# SCH_keyboard_2024-02-28.net
KiCad netlist of a schematic drawn in EasyEDA
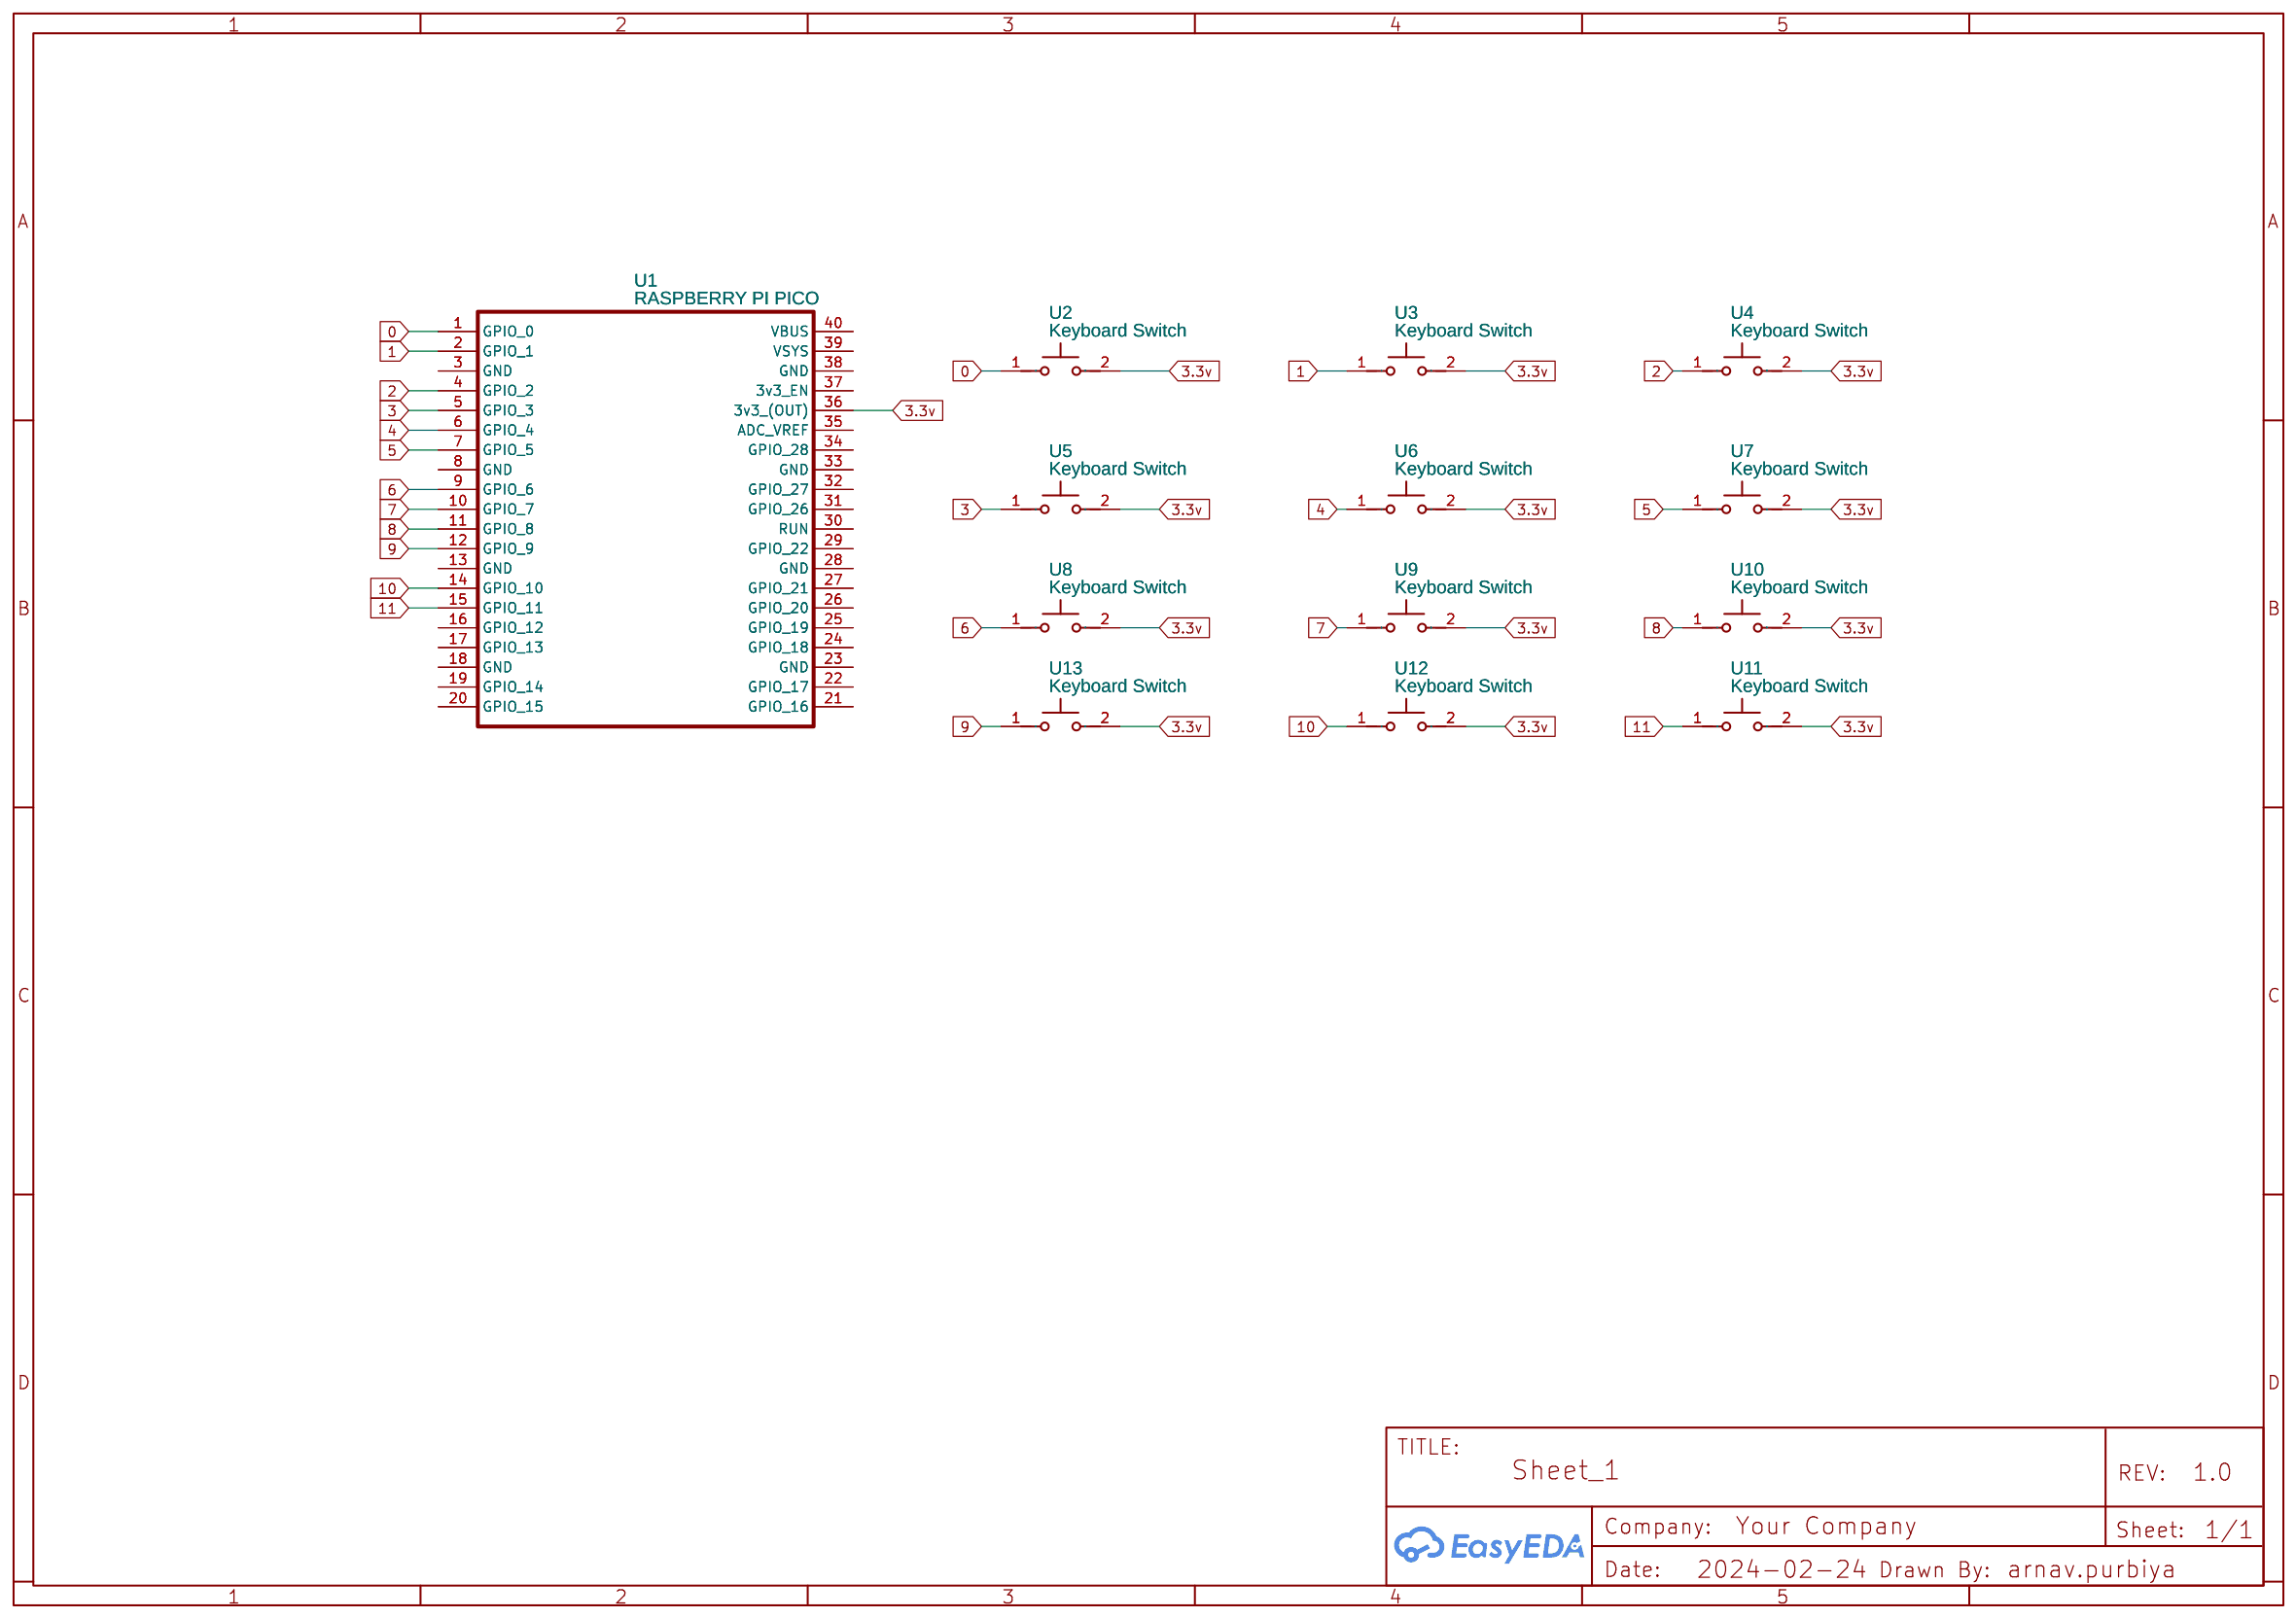
[diagram p0: schematic sheet]

(export (version "E")
  (design (tool "Eeschema 10.0.6"))
  (components
    (comp (ref "U1") (value "RASPBERRY PI PICO") (libsource (lib "") (part "RASPBERRY PI PICO")))
    (comp (ref "U2")
      (value "Keyboard Switch")
      (fields (field (name "Manufacturer") "HepLer"))
      (libsource (lib "") (part "Keyboard Switch"))
    )
    (comp (ref "U3")
      (value "Keyboard Switch")
      (fields (field (name "Manufacturer") "HepLer"))
      (libsource (lib "") (part "Keyboard Switch"))
    )
    (comp (ref "U4")
      (value "Keyboard Switch")
      (fields (field (name "Manufacturer") "HepLer"))
      (libsource (lib "") (part "Keyboard Switch"))
    )
    (comp (ref "U5")
      (value "Keyboard Switch")
      (fields (field (name "Manufacturer") "HepLer"))
      (libsource (lib "") (part "Keyboard Switch"))
    )
    (comp (ref "U6")
      (value "Keyboard Switch")
      (fields (field (name "Manufacturer") "HepLer"))
      (libsource (lib "") (part "Keyboard Switch"))
    )
    (comp (ref "U7")
      (value "Keyboard Switch")
      (fields (field (name "Manufacturer") "HepLer"))
      (libsource (lib "") (part "Keyboard Switch"))
    )
    (comp (ref "U8")
      (value "Keyboard Switch")
      (fields (field (name "Manufacturer") "HepLer"))
      (libsource (lib "") (part "Keyboard Switch"))
    )
    (comp (ref "U9")
      (value "Keyboard Switch")
      (fields (field (name "Manufacturer") "HepLer"))
      (libsource (lib "") (part "Keyboard Switch"))
    )
    (comp (ref "U10")
      (value "Keyboard Switch")
      (fields (field (name "Manufacturer") "HepLer"))
      (libsource (lib "") (part "Keyboard Switch"))
    )
    (comp (ref "U11")
      (value "Keyboard Switch")
      (fields (field (name "Manufacturer") "HepLer"))
      (libsource (lib "") (part "Keyboard Switch"))
    )
    (comp (ref "U12")
      (value "Keyboard Switch")
      (fields (field (name "Manufacturer") "HepLer"))
      (libsource (lib "") (part "Keyboard Switch"))
    )
    (comp (ref "U13")
      (value "Keyboard Switch")
      (fields (field (name "Manufacturer") "HepLer"))
      (libsource (lib "") (part "Keyboard Switch"))
    )
  )
  (nets
    (net (code "1") (name "0") (class "Default")
      (node (ref "U1") (pin "1") (pinfunction "GPIO_0_1") (pintype "unspecified"))
      (node (ref "U2") (pin "1") (pinfunction "1_1") (pintype "unspecified"))
    )
    (net (code "2") (name "1") (class "Default")
      (node (ref "U1") (pin "2") (pinfunction "GPIO_1_2") (pintype "unspecified"))
      (node (ref "U3") (pin "1") (pinfunction "1_1") (pintype "unspecified"))
    )
    (net (code "3") (name "2") (class "Default")
      (node (ref "U1") (pin "4") (pinfunction "GPIO_2_4") (pintype "unspecified"))
      (node (ref "U4") (pin "1") (pinfunction "1_1") (pintype "unspecified"))
    )
    (net (code "4") (name "3") (class "Default")
      (node (ref "U1") (pin "5") (pinfunction "GPIO_3_5") (pintype "unspecified"))
      (node (ref "U5") (pin "1") (pinfunction "1_1") (pintype "unspecified"))
    )
    (net (code "5") (name "3.3v") (class "Default")
      (node (ref "U1") (pin "36") (pinfunction "3v3_(OUT)_36") (pintype "unspecified"))
      (node (ref "U10") (pin "2") (pinfunction "2_2") (pintype "unspecified"))
      (node (ref "U11") (pin "2") (pinfunction "2_2") (pintype "unspecified"))
      (node (ref "U12") (pin "2") (pinfunction "2_2") (pintype "unspecified"))
      (node (ref "U13") (pin "2") (pinfunction "2_2") (pintype "unspecified"))
      (node (ref "U2") (pin "2") (pinfunction "2_2") (pintype "unspecified"))
      (node (ref "U3") (pin "2") (pinfunction "2_2") (pintype "unspecified"))
      (node (ref "U4") (pin "2") (pinfunction "2_2") (pintype "unspecified"))
      (node (ref "U5") (pin "2") (pinfunction "2_2") (pintype "unspecified"))
      (node (ref "U6") (pin "2") (pinfunction "2_2") (pintype "unspecified"))
      (node (ref "U7") (pin "2") (pinfunction "2_2") (pintype "unspecified"))
      (node (ref "U8") (pin "2") (pinfunction "2_2") (pintype "unspecified"))
      (node (ref "U9") (pin "2") (pinfunction "2_2") (pintype "unspecified"))
    )
    (net (code "6") (name "4") (class "Default")
      (node (ref "U1") (pin "6") (pinfunction "GPIO_4_6") (pintype "unspecified"))
      (node (ref "U6") (pin "1") (pinfunction "1_1") (pintype "unspecified"))
    )
    (net (code "7") (name "5") (class "Default")
      (node (ref "U1") (pin "7") (pinfunction "GPIO_5_7") (pintype "unspecified"))
      (node (ref "U7") (pin "1") (pinfunction "1_1") (pintype "unspecified"))
    )
    (net (code "8") (name "6") (class "Default")
      (node (ref "U1") (pin "9") (pinfunction "GPIO_6_9") (pintype "unspecified"))
      (node (ref "U8") (pin "1") (pinfunction "1_1") (pintype "unspecified"))
    )
    (net (code "9") (name "7") (class "Default")
      (node (ref "U1") (pin "10") (pinfunction "GPIO_7_10") (pintype "unspecified"))
      (node (ref "U9") (pin "1") (pinfunction "1_1") (pintype "unspecified"))
    )
    (net (code "10") (name "8") (class "Default")
      (node (ref "U1") (pin "11") (pinfunction "GPIO_8_11") (pintype "unspecified"))
      (node (ref "U10") (pin "1") (pinfunction "1_1") (pintype "unspecified"))
    )
    (net (code "11") (name "9") (class "Default")
      (node (ref "U1") (pin "12") (pinfunction "GPIO_9_12") (pintype "unspecified"))
      (node (ref "U13") (pin "1") (pinfunction "1_1") (pintype "unspecified"))
    )
    (net (code "12") (name "10") (class "Default")
      (node (ref "U1") (pin "14") (pinfunction "GPIO_10_14") (pintype "unspecified"))
      (node (ref "U12") (pin "1") (pinfunction "1_1") (pintype "unspecified"))
    )
    (net (code "13") (name "11") (class "Default")
      (node (ref "U1") (pin "15") (pinfunction "GPIO_11_15") (pintype "unspecified"))
      (node (ref "U11") (pin "1") (pinfunction "1_1") (pintype "unspecified"))
    )
    (net (code "14") (name "unconnected-(U1-3v3_EN-Pad37)") (class "Default")
      (node (ref "U1") (pin "37") (pinfunction "3v3_EN_37") (pintype "unspecified"))
    )
    (net (code "15") (name "unconnected-(U1-ADC_VREF-Pad35)") (class "Default")
      (node (ref "U1") (pin "35") (pinfunction "ADC_VREF_35") (pintype "unspecified"))
    )
    (net (code "16") (name "unconnected-(U1-GND-Pad3)") (class "Default")
      (node (ref "U1") (pin "3") (pinfunction "GND_3") (pintype "unspecified"))
    )
    (net (code "17") (name "unconnected-(U1-GND-Pad8)") (class "Default")
      (node (ref "U1") (pin "8") (pinfunction "GND_8") (pintype "unspecified"))
    )
    (net (code "18") (name "unconnected-(U1-GND-Pad13)") (class "Default")
      (node (ref "U1") (pin "13") (pinfunction "GND_13") (pintype "unspecified"))
    )
    (net (code "19") (name "unconnected-(U1-GND-Pad18)") (class "Default")
      (node (ref "U1") (pin "18") (pinfunction "GND_18") (pintype "unspecified"))
    )
    (net (code "20") (name "unconnected-(U1-GND-Pad23)") (class "Default")
      (node (ref "U1") (pin "23") (pinfunction "GND_23") (pintype "unspecified"))
    )
    (net (code "21") (name "unconnected-(U1-GND-Pad28)") (class "Default")
      (node (ref "U1") (pin "28") (pinfunction "GND_28") (pintype "unspecified"))
    )
    (net (code "22") (name "unconnected-(U1-GND-Pad33)") (class "Default")
      (node (ref "U1") (pin "33") (pinfunction "GND_33") (pintype "unspecified"))
    )
    (net (code "23") (name "unconnected-(U1-GND-Pad38)") (class "Default")
      (node (ref "U1") (pin "38") (pinfunction "GND_38") (pintype "unspecified"))
    )
    (net (code "24") (name "unconnected-(U1-GPIO_12-Pad16)") (class "Default")
      (node (ref "U1") (pin "16") (pinfunction "GPIO_12_16") (pintype "unspecified"))
    )
    (net (code "25") (name "unconnected-(U1-GPIO_13-Pad17)") (class "Default")
      (node (ref "U1") (pin "17") (pinfunction "GPIO_13_17") (pintype "unspecified"))
    )
    (net (code "26") (name "unconnected-(U1-GPIO_14-Pad19)") (class "Default")
      (node (ref "U1") (pin "19") (pinfunction "GPIO_14_19") (pintype "unspecified"))
    )
    (net (code "27") (name "unconnected-(U1-GPIO_15-Pad20)") (class "Default")
      (node (ref "U1") (pin "20") (pinfunction "GPIO_15_20") (pintype "unspecified"))
    )
    (net (code "28") (name "unconnected-(U1-GPIO_16-Pad21)") (class "Default")
      (node (ref "U1") (pin "21") (pinfunction "GPIO_16_21") (pintype "unspecified"))
    )
    (net (code "29") (name "unconnected-(U1-GPIO_17-Pad22)") (class "Default")
      (node (ref "U1") (pin "22") (pinfunction "GPIO_17_22") (pintype "unspecified"))
    )
    (net (code "30") (name "unconnected-(U1-GPIO_18-Pad24)") (class "Default")
      (node (ref "U1") (pin "24") (pinfunction "GPIO_18_24") (pintype "unspecified"))
    )
    (net (code "31") (name "unconnected-(U1-GPIO_19-Pad25)") (class "Default")
      (node (ref "U1") (pin "25") (pinfunction "GPIO_19_25") (pintype "unspecified"))
    )
    (net (code "32") (name "unconnected-(U1-GPIO_20-Pad26)") (class "Default")
      (node (ref "U1") (pin "26") (pinfunction "GPIO_20_26") (pintype "unspecified"))
    )
    (net (code "33") (name "unconnected-(U1-GPIO_21-Pad27)") (class "Default")
      (node (ref "U1") (pin "27") (pinfunction "GPIO_21_27") (pintype "unspecified"))
    )
    (net (code "34") (name "unconnected-(U1-GPIO_22-Pad29)") (class "Default")
      (node (ref "U1") (pin "29") (pinfunction "GPIO_22_29") (pintype "unspecified"))
    )
    (net (code "35") (name "unconnected-(U1-GPIO_26-Pad31)") (class "Default")
      (node (ref "U1") (pin "31") (pinfunction "GPIO_26_31") (pintype "unspecified"))
    )
    (net (code "36") (name "unconnected-(U1-GPIO_27-Pad32)") (class "Default")
      (node (ref "U1") (pin "32") (pinfunction "GPIO_27_32") (pintype "unspecified"))
    )
    (net (code "37") (name "unconnected-(U1-GPIO_28-Pad34)") (class "Default")
      (node (ref "U1") (pin "34") (pinfunction "GPIO_28_34") (pintype "unspecified"))
    )
    (net (code "38") (name "unconnected-(U1-RUN-Pad30)") (class "Default")
      (node (ref "U1") (pin "30") (pinfunction "RUN_30") (pintype "unspecified"))
    )
    (net (code "39") (name "unconnected-(U1-VBUS-Pad40)") (class "Default")
      (node (ref "U1") (pin "40") (pinfunction "VBUS_40") (pintype "unspecified"))
    )
    (net (code "40") (name "unconnected-(U1-VSYS-Pad39)") (class "Default")
      (node (ref "U1") (pin "39") (pinfunction "VSYS_39") (pintype "unspecified"))
    )
  )
)
